# DriverSPI.net
KiCad netlist of a schematic drawn in Altium Designer
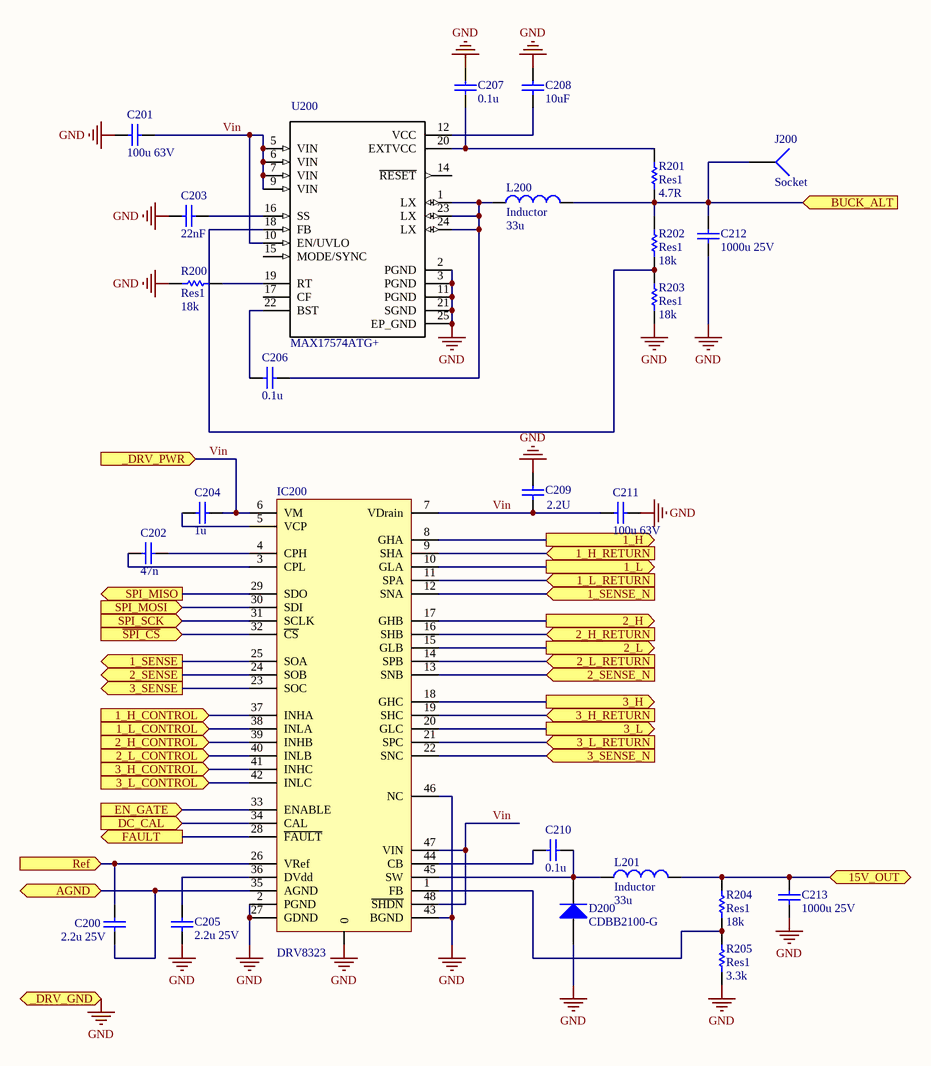
[diagram p0: DriverSPI.SchDoc]

(export (version "E")
  (design (tool "Eeschema 10.0.6"))
  (components
    (comp (ref "C200")
      (value "2.2u 25V")
      (footprint "1206x")
      (description "Capacitor")
      (fields (field (name "PUBLISHER") "Altium Limited"))
      (libsource (lib "Miscellaneous Devices") (part "Cap"))
    )
    (comp (ref "C201")
      (value "100u 63V")
      (footprint "CAP_ELEC_10mm")
      (description "Capacitor")
      (fields (field (name "PUBLISHER") "Altium Limited"))
      (libsource (lib "Miscellaneous Devices") (part "Cap"))
    )
    (comp (ref "C202")
      (value "47n")
      (footprint "0603x")
      (description "Capacitor")
      (fields (field (name "PUBLISHER") "Altium Limited"))
      (libsource (lib "Miscellaneous Devices") (part "Cap"))
    )
    (comp (ref "C203")
      (value "22nF")
      (footprint "0603x")
      (description "Capacitor")
      (fields (field (name "PUBLISHER") "Altium Limited"))
      (libsource (lib "Miscellaneous Devices") (part "Cap"))
    )
    (comp (ref "C204")
      (value "1u")
      (footprint "0805x")
      (description "Capacitor")
      (fields (field (name "PUBLISHER") "Altium Limited"))
      (libsource (lib "Miscellaneous Devices") (part "Cap"))
    )
    (comp (ref "C205")
      (value "2.2u 25V")
      (footprint "1206x")
      (description "Capacitor")
      (fields (field (name "PUBLISHER") "Altium Limited"))
      (libsource (lib "Miscellaneous Devices") (part "Cap"))
    )
    (comp (ref "C206")
      (value "0.1u")
      (footprint "0603x")
      (description "Capacitor")
      (fields (field (name "PUBLISHER") "Altium Limited"))
      (libsource (lib "Miscellaneous Devices") (part "Cap"))
    )
    (comp (ref "C207")
      (value "0.1u")
      (footprint "0603x")
      (description "Capacitor")
      (fields (field (name "PUBLISHER") "Altium Limited"))
      (libsource (lib "Miscellaneous Devices") (part "Cap"))
    )
    (comp (ref "C208")
      (value "10uF")
      (footprint "1206x")
      (description "Capacitor")
      (fields (field (name "PUBLISHER") "Altium Limited"))
      (libsource (lib "Miscellaneous Devices") (part "Cap"))
    )
    (comp (ref "C209")
      (value "2.2U")
      (footprint "1210")
      (description "Capacitor")
      (fields (field (name "PUBLISHER") "Altium Limited"))
      (libsource (lib "Miscellaneous Devices") (part "Cap"))
    )
    (comp (ref "C210")
      (value "0.1u")
      (footprint "0603x")
      (description "Capacitor")
      (fields (field (name "PUBLISHER") "Altium Limited"))
      (libsource (lib "Miscellaneous Devices") (part "Cap"))
    )
    (comp (ref "C211")
      (value "100u 63V")
      (footprint "CAP_ELEC_10mm")
      (description "Capacitor")
      (fields (field (name "PUBLISHER") "Altium Limited"))
      (libsource (lib "Miscellaneous Devices") (part "Cap"))
    )
    (comp (ref "C212")
      (value "1000u 25V")
      (footprint "CAP_ELEC_10mm")
      (description "Capacitor")
      (fields (field (name "PUBLISHER") "Altium Limited"))
      (libsource (lib "Miscellaneous Devices") (part "Cap"))
    )
    (comp (ref "C213")
      (value "1000u 25V")
      (footprint "CAP_ELEC_10mm")
      (description "Capacitor")
      (fields (field (name "PUBLISHER") "Altium Limited"))
      (libsource (lib "Miscellaneous Devices") (part "Cap"))
    )
    (comp (ref "D200")
      (value "CDBB2100-G")
      (footprint "SMB_real")
      (description "Default Diode")
      (fields (field (name "PUBLISHER") "Altium Limited"))
      (libsource (lib "Miscellaneous Devices") (part "Diode"))
    )
    (comp (ref "IC200") (value "DRV8323") (footprint "PWQFN-48") (libsource (lib "EDDLib") (part "DRV8323")))
    (comp (ref "J200")
      (value "Socket")
      (footprint "PIN1")
      (fields (field (name "PUBLISHER") "Altium Limited"))
      (libsource (lib "Miscellaneous Connectors") (part "Socket"))
    )
    (comp (ref "L200")
      (value "Inductor")
      (footprint "DR74")
      (fields (field (name "ALTIUM_VALUE") "33u") (field (name "PUBLISHER") "Altium Limited"))
      (libsource (lib "Miscellaneous Devices") (part "Inductor"))
    )
    (comp (ref "L201")
      (value "Inductor")
      (footprint "DR74")
      (fields (field (name "ALTIUM_VALUE") "33u") (field (name "PUBLISHER") "Altium Limited"))
      (libsource (lib "Miscellaneous Devices") (part "Inductor"))
    )
    (comp (ref "R200")
      (value "Res1")
      (footprint "0603x")
      (description "Resistor")
      (fields (field (name "ALTIUM_VALUE") "18k") (field (name "PUBLISHER") "Altium Limited"))
      (libsource (lib "Miscellaneous Devices") (part "Res1"))
    )
    (comp (ref "R201")
      (value "Res1")
      (footprint "0603x")
      (description "Resistor")
      (fields (field (name "ALTIUM_VALUE") "4.7R") (field (name "PUBLISHER") "Altium Limited"))
      (libsource (lib "Miscellaneous Devices") (part "Res1"))
    )
    (comp (ref "R202")
      (value "Res1")
      (footprint "0603x")
      (description "Resistor")
      (fields (field (name "ALTIUM_VALUE") "18k") (field (name "PUBLISHER") "Altium Limited"))
      (libsource (lib "Miscellaneous Devices") (part "Res1"))
    )
    (comp (ref "R203")
      (value "Res1")
      (footprint "0603x")
      (description "Resistor")
      (fields (field (name "ALTIUM_VALUE") "18k") (field (name "PUBLISHER") "Altium Limited"))
      (libsource (lib "Miscellaneous Devices") (part "Res1"))
    )
    (comp (ref "R204")
      (value "Res1")
      (footprint "0603x")
      (description "Resistor")
      (fields (field (name "ALTIUM_VALUE") "18k") (field (name "PUBLISHER") "Altium Limited"))
      (libsource (lib "Miscellaneous Devices") (part "Res1"))
    )
    (comp (ref "R205")
      (value "Res1")
      (footprint "0603x")
      (description "Resistor")
      (fields (field (name "ALTIUM_VALUE") "3.3k") (field (name "PUBLISHER") "Altium Limited"))
      (libsource (lib "Miscellaneous Devices") (part "Res1"))
    )
    (comp (ref "U200")
      (value "MAX17574ATG+")
      (footprint "QFN50P500X400X80-25N")
      (description "IC REG BUCK ADJ 3A SYNC 24TQFN")
      (fields (field (name "DIGI-KEY_PART_NUMBER") "MAX17574ATG+-ND") (field (name "MF") "Maxim Integrated"))
      (libsource (lib "MAX17574ATG_") (part "MAX17574ATG+"))
    )
  )
  (nets
    (net (code "1") (name "/1_H") (class "Default")
      (node (ref "IC200") (pin "8") (pinfunction "GHA_8") (pintype "passive"))
    )
    (net (code "2") (name "/1_H_CONTROL") (class "Default")
      (node (ref "IC200") (pin "37") (pinfunction "INHA_37") (pintype "passive"))
    )
    (net (code "3") (name "/1_H_RETURN") (class "Default")
      (node (ref "IC200") (pin "9") (pinfunction "SHA_9") (pintype "passive"))
    )
    (net (code "4") (name "/1_L") (class "Default")
      (node (ref "IC200") (pin "10") (pinfunction "GLA_10") (pintype "passive"))
    )
    (net (code "5") (name "/1_L_CONTROL") (class "Default")
      (node (ref "IC200") (pin "38") (pinfunction "INLA_38") (pintype "passive"))
    )
    (net (code "6") (name "/1_L_RETURN") (class "Default")
      (node (ref "IC200") (pin "11") (pinfunction "SPA_11") (pintype "passive"))
    )
    (net (code "7") (name "/1_SENSE") (class "Default")
      (node (ref "IC200") (pin "25") (pinfunction "SOA_25") (pintype "passive"))
    )
    (net (code "8") (name "/1_SENSE_N") (class "Default")
      (node (ref "IC200") (pin "12") (pinfunction "SNA_12") (pintype "passive"))
    )
    (net (code "9") (name "/2_H") (class "Default")
      (node (ref "IC200") (pin "17") (pinfunction "GHB_17") (pintype "passive"))
    )
    (net (code "10") (name "/2_H_CONTROL") (class "Default")
      (node (ref "IC200") (pin "39") (pinfunction "INHB_39") (pintype "passive"))
    )
    (net (code "11") (name "/2_H_RETURN") (class "Default")
      (node (ref "IC200") (pin "16") (pinfunction "SHB_16") (pintype "passive"))
    )
    (net (code "12") (name "/2_L") (class "Default")
      (node (ref "IC200") (pin "15") (pinfunction "GLB_15") (pintype "passive"))
    )
    (net (code "13") (name "/2_L_CONTROL") (class "Default")
      (node (ref "IC200") (pin "40") (pinfunction "INLB_40") (pintype "passive"))
    )
    (net (code "14") (name "/2_L_RETURN") (class "Default")
      (node (ref "IC200") (pin "14") (pinfunction "SPB_14") (pintype "passive"))
    )
    (net (code "15") (name "/2_SENSE") (class "Default")
      (node (ref "IC200") (pin "24") (pinfunction "SOB_24") (pintype "passive"))
    )
    (net (code "16") (name "/2_SENSE_N") (class "Default")
      (node (ref "IC200") (pin "13") (pinfunction "SNB_13") (pintype "passive"))
    )
    (net (code "17") (name "/3_H") (class "Default")
      (node (ref "IC200") (pin "18") (pinfunction "GHC_18") (pintype "passive"))
    )
    (net (code "18") (name "/3_H_CONTROL") (class "Default")
      (node (ref "IC200") (pin "41") (pinfunction "INHC_41") (pintype "passive"))
    )
    (net (code "19") (name "/3_H_RETURN") (class "Default")
      (node (ref "IC200") (pin "19") (pinfunction "SHC_19") (pintype "passive"))
    )
    (net (code "20") (name "/3_L") (class "Default")
      (node (ref "IC200") (pin "20") (pinfunction "GLC_20") (pintype "passive"))
    )
    (net (code "21") (name "/3_L_CONTROL") (class "Default")
      (node (ref "IC200") (pin "42") (pinfunction "INLC_42") (pintype "passive"))
    )
    (net (code "22") (name "/3_L_RETURN") (class "Default")
      (node (ref "IC200") (pin "21") (pinfunction "SPC_21") (pintype "passive"))
    )
    (net (code "23") (name "/3_SENSE") (class "Default")
      (node (ref "IC200") (pin "23") (pinfunction "SOC_23") (pintype "passive"))
    )
    (net (code "24") (name "/3_SENSE_N") (class "Default")
      (node (ref "IC200") (pin "22") (pinfunction "SNC_22") (pintype "passive"))
    )
    (net (code "25") (name "/15V_OUT") (class "Default")
      (node (ref "C213") (pin "1") (pinfunction "1_1") (pintype "passive"))
      (node (ref "L201") (pin "2") (pinfunction "2_2") (pintype "passive"))
      (node (ref "R204") (pin "2") (pinfunction "2_2") (pintype "passive"))
    )
    (net (code "26") (name "/AGND") (class "Default")
      (node (ref "C200") (pin "1") (pinfunction "1_1") (pintype "passive"))
      (node (ref "IC200") (pin "35") (pinfunction "AGND_35") (pintype "passive"))
    )
    (net (code "27") (name "/BUCK_ALT") (class "Default")
      (node (ref "C212") (pin "1") (pinfunction "1_1") (pintype "passive"))
      (node (ref "J200") (pin "1") (pinfunction "1_1") (pintype "passive"))
      (node (ref "L200") (pin "2") (pinfunction "2_2") (pintype "passive"))
      (node (ref "R201") (pin "2") (pinfunction "2_2") (pintype "passive"))
      (node (ref "R202") (pin "2") (pinfunction "2_2") (pintype "passive"))
    )
    (net (code "28") (name "/DC_CAL") (class "Default")
      (node (ref "IC200") (pin "34") (pinfunction "CAL_34") (pintype "passive"))
    )
    (net (code "29") (name "/EN_GATE") (class "Default")
      (node (ref "IC200") (pin "33") (pinfunction "ENABLE_33") (pintype "passive"))
    )
    (net (code "30") (name "/FAULT") (class "Default")
      (node (ref "IC200") (pin "28") (pinfunction "~{FAULT}_28") (pintype "passive"))
    )
    (net (code "31") (name "/Ref") (class "Default")
      (node (ref "C200") (pin "2") (pinfunction "2_2") (pintype "passive"))
      (node (ref "IC200") (pin "26") (pinfunction "VRef_26") (pintype "passive"))
    )
    (net (code "32") (name "/SPI_MISO") (class "Default")
      (node (ref "IC200") (pin "29") (pinfunction "SDO_29") (pintype "passive"))
    )
    (net (code "33") (name "/SPI_MOSI") (class "Default")
      (node (ref "IC200") (pin "30") (pinfunction "SDI_30") (pintype "passive"))
    )
    (net (code "34") (name "/SPI_SCK") (class "Default")
      (node (ref "IC200") (pin "31") (pinfunction "SCLK_31") (pintype "passive"))
    )
    (net (code "35") (name "/Vin") (class "Default")
      (node (ref "C201") (pin "1") (pinfunction "1_1") (pintype "passive"))
      (node (ref "C204") (pin "2") (pinfunction "2_2") (pintype "passive"))
      (node (ref "C209") (pin "1") (pinfunction "1_1") (pintype "passive"))
      (node (ref "C211") (pin "2") (pinfunction "2_2") (pintype "passive"))
      (node (ref "IC200") (pin "47") (pinfunction "VIN_47") (pintype "passive"))
      (node (ref "IC200") (pin "48") (pinfunction "~{SHDN}_48") (pintype "passive"))
      (node (ref "IC200") (pin "6") (pinfunction "VM_6") (pintype "passive"))
      (node (ref "IC200") (pin "7") (pinfunction "VDrain_7") (pintype "passive"))
      (node (ref "U200") (pin "10") (pinfunction "EN/UVLO_10") (pintype "input"))
      (node (ref "U200") (pin "5") (pinfunction "VIN_5") (pintype "input"))
      (node (ref "U200") (pin "6") (pinfunction "VIN_6") (pintype "input"))
      (node (ref "U200") (pin "7") (pinfunction "VIN_7") (pintype "input"))
      (node (ref "U200") (pin "9") (pinfunction "VIN_9") (pintype "input"))
    )
    (net (code "36") (name "/~{SPI_CS}") (class "Default")
      (node (ref "IC200") (pin "32") (pinfunction "~{CS}_32") (pintype "passive"))
    )
    (net (code "37") (name "GND") (class "Default")
      (node (ref "C201") (pin "2") (pinfunction "2_2") (pintype "passive"))
      (node (ref "C203") (pin "1") (pinfunction "1_1") (pintype "passive"))
      (node (ref "C205") (pin "1") (pinfunction "1_1") (pintype "passive"))
      (node (ref "C207") (pin "2") (pinfunction "2_2") (pintype "passive"))
      (node (ref "C208") (pin "2") (pinfunction "2_2") (pintype "passive"))
      (node (ref "C209") (pin "2") (pinfunction "2_2") (pintype "passive"))
      (node (ref "C211") (pin "1") (pinfunction "1_1") (pintype "passive"))
      (node (ref "C212") (pin "2") (pinfunction "2_2") (pintype "passive"))
      (node (ref "C213") (pin "2") (pinfunction "2_2") (pintype "passive"))
      (node (ref "D200") (pin "1") (pinfunction "A_1") (pintype "passive"))
      (node (ref "IC200") (pin "0") (pinfunction "0_0") (pintype "passive"))
      (node (ref "IC200") (pin "2") (pinfunction "PGND_2") (pintype "passive"))
      (node (ref "IC200") (pin "27") (pinfunction "GDND_27") (pintype "passive"))
      (node (ref "IC200") (pin "43") (pinfunction "BGND_43") (pintype "passive"))
      (node (ref "IC200") (pin "46") (pinfunction "NC_46") (pintype "passive"))
      (node (ref "R200") (pin "2") (pinfunction "2_2") (pintype "passive"))
      (node (ref "R203") (pin "1") (pinfunction "1_1") (pintype "passive"))
      (node (ref "R205") (pin "1") (pinfunction "1_1") (pintype "passive"))
      (node (ref "U200") (pin "11") (pinfunction "PGND_11") (pintype "power_in"))
      (node (ref "U200") (pin "2") (pinfunction "PGND_2") (pintype "power_in"))
      (node (ref "U200") (pin "21") (pinfunction "SGND_21") (pintype "power_in"))
      (node (ref "U200") (pin "25") (pinfunction "EP_GND_25") (pintype "power_in"))
      (node (ref "U200") (pin "3") (pinfunction "PGND_3") (pintype "power_in"))
    )
    (net (code "38") (name "Net-(C206-Pad2)") (class "Default")
      (node (ref "C206") (pin "2") (pinfunction "2_2") (pintype "passive"))
      (node (ref "L200") (pin "1") (pinfunction "1_1") (pintype "passive"))
      (node (ref "U200") (pin "1") (pinfunction "LX_1") (pintype "bidirectional"))
      (node (ref "U200") (pin "23") (pinfunction "LX_23") (pintype "bidirectional"))
      (node (ref "U200") (pin "24") (pinfunction "LX_24") (pintype "bidirectional"))
    )
    (net (code "39") (name "Net-(D200-K)") (class "Default")
      (node (ref "C210") (pin "2") (pinfunction "2_2") (pintype "passive"))
      (node (ref "D200") (pin "2") (pinfunction "K_2") (pintype "passive"))
      (node (ref "IC200") (pin "45") (pinfunction "SW_45") (pintype "passive"))
      (node (ref "L201") (pin "1") (pinfunction "1_1") (pintype "passive"))
    )
    (net (code "40") (name "Net-(IC200-CB)") (class "Default")
      (node (ref "C210") (pin "1") (pinfunction "1_1") (pintype "passive"))
      (node (ref "IC200") (pin "44") (pinfunction "CB_44") (pintype "passive"))
    )
    (net (code "41") (name "Net-(IC200-CPH)") (class "Default")
      (node (ref "C202") (pin "2") (pinfunction "2_2") (pintype "passive"))
      (node (ref "IC200") (pin "4") (pinfunction "CPH_4") (pintype "passive"))
    )
    (net (code "42") (name "Net-(IC200-CPL)") (class "Default")
      (node (ref "C202") (pin "1") (pinfunction "1_1") (pintype "passive"))
      (node (ref "IC200") (pin "3") (pinfunction "CPL_3") (pintype "passive"))
    )
    (net (code "43") (name "Net-(IC200-DVdd)") (class "Default")
      (node (ref "C205") (pin "2") (pinfunction "2_2") (pintype "passive"))
      (node (ref "IC200") (pin "36") (pinfunction "DVdd_36") (pintype "passive"))
    )
    (net (code "44") (name "Net-(IC200-FB)") (class "Default")
      (node (ref "IC200") (pin "1") (pinfunction "FB_1") (pintype "passive"))
      (node (ref "R204") (pin "1") (pinfunction "1_1") (pintype "passive"))
      (node (ref "R205") (pin "2") (pinfunction "2_2") (pintype "passive"))
    )
    (net (code "45") (name "Net-(IC200-VCP)") (class "Default")
      (node (ref "C204") (pin "1") (pinfunction "1_1") (pintype "passive"))
      (node (ref "IC200") (pin "5") (pinfunction "VCP_5") (pintype "passive"))
    )
    (net (code "46") (name "Net-(U200-BST)") (class "Default")
      (node (ref "C206") (pin "1") (pinfunction "1_1") (pintype "passive"))
      (node (ref "U200") (pin "22") (pinfunction "BST_22") (pintype "passive"))
    )
    (net (code "47") (name "Net-(U200-EXTVCC)") (class "Default")
      (node (ref "C207") (pin "1") (pinfunction "1_1") (pintype "passive"))
      (node (ref "R201") (pin "1") (pinfunction "1_1") (pintype "passive"))
      (node (ref "U200") (pin "20") (pinfunction "EXTVCC_20") (pintype "power_in"))
    )
    (net (code "48") (name "Net-(U200-FB)") (class "Default")
      (node (ref "R202") (pin "1") (pinfunction "1_1") (pintype "passive"))
      (node (ref "R203") (pin "2") (pinfunction "2_2") (pintype "passive"))
      (node (ref "U200") (pin "18") (pinfunction "FB_18") (pintype "input"))
    )
    (net (code "49") (name "Net-(U200-RT)") (class "Default")
      (node (ref "R200") (pin "1") (pinfunction "1_1") (pintype "passive"))
      (node (ref "U200") (pin "19") (pinfunction "RT_19") (pintype "passive"))
    )
    (net (code "50") (name "Net-(U200-SS)") (class "Default")
      (node (ref "C203") (pin "2") (pinfunction "2_2") (pintype "passive"))
      (node (ref "U200") (pin "16") (pinfunction "SS_16") (pintype "input"))
    )
    (net (code "51") (name "Net-(U200-VCC)") (class "Default")
      (node (ref "C208") (pin "1") (pinfunction "1_1") (pintype "passive"))
      (node (ref "U200") (pin "12") (pinfunction "VCC_12") (pintype "power_in"))
    )
    (net (code "52") (name "unconnected-(U200-CF-Pad17)") (class "Default")
      (node (ref "U200") (pin "17") (pinfunction "CF_17") (pintype "passive"))
    )
    (net (code "53") (name "unconnected-(U200-MODE{slash}SYNC-Pad15)") (class "Default")
      (node (ref "U200") (pin "15") (pinfunction "MODE/SYNC_15") (pintype "input"))
    )
    (net (code "54") (name "unconnected-(U200-~{RESET}-Pad14)") (class "Default")
      (node (ref "U200") (pin "14") (pinfunction "~{RESET}_14") (pintype "output"))
    )
  )
)
